# Lipo_Charger1.net
KiCad netlist of a schematic drawn in Altium Designer
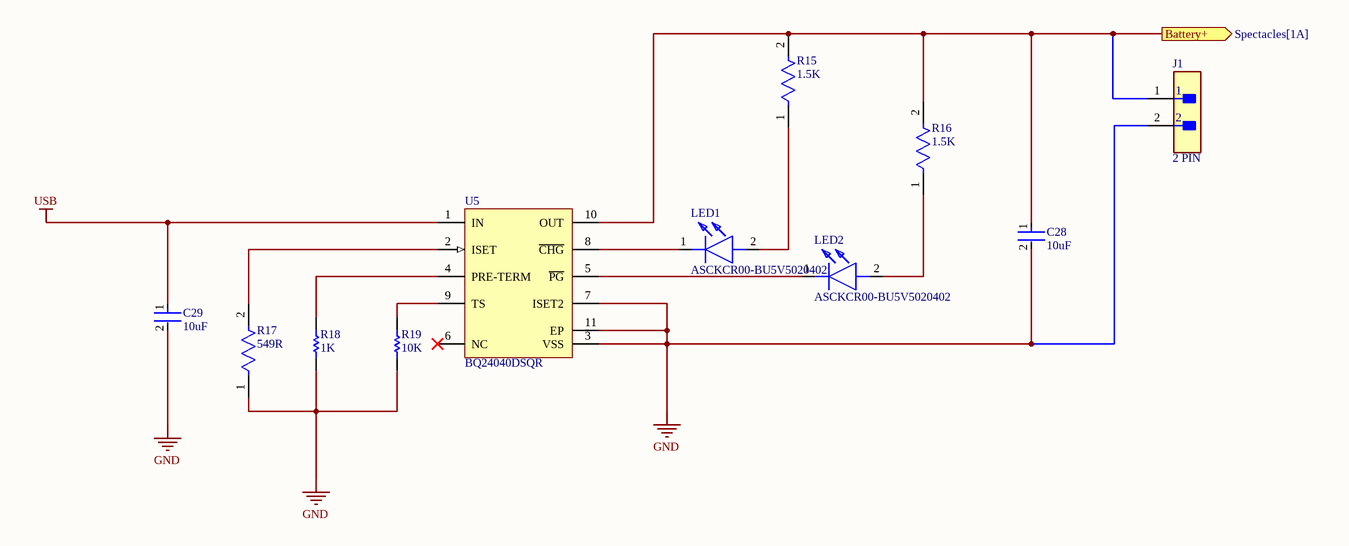
[diagram p0: Lipo Charger1.SchDoc]

(export (version "E")
  (design (tool "Eeschema 10.0.6"))
  (components
    (comp (ref "C28")
      (value "10uF")
      (footprint "FP-CL10-IPC_A")
      (description "Cap Ceramic 100nF 50V X7R ±10% Pad SMD 0603 +125°C T/R")
      (fields (field (name "VOLTAGE") "50V") (field (name "TOLERANCE") "10%"))
      (libsource (lib "Altium Content Vault") (part "b4654b650e69147ec39a6b967a45e02"))
    )
    (comp (ref "C29")
      (value "10uF")
      (footprint "FP-CL10-IPC_A")
      (description "Cap Ceramic 100nF 50V X7R ±10% Pad SMD 0603 +125°C T/R")
      (fields (field (name "VOLTAGE") "50V") (field (name "TOLERANCE") "10%"))
      (libsource (lib "Altium Content Vault") (part "b4654b650e69147ec39a6b967a45e02"))
    )
    (comp (ref "J1")
      (value "2 PIN")
      (footprint "FP-B2B-XH-AM_LF_SN-MFG")
      (description "CONN HEADER VERT 2POS 2.5MM")
      (libsource (lib "Altium Content Vault") (part "3bc925449376181038e59eaffc5286c"))
    )
    (comp (ref "LED1")
      (value "ASCKCR00-BU5V5020402")
      (footprint "SamacSys:ASCKCR00BU5V5020402")
      (description "LED")
      (fields (field (name "MOUSER PART NUMBER") "630-ASCKCR00BU5V5020"))
      (libsource (lib "*") (part "ASCKCR00-BU5V5020402"))
    )
    (comp (ref "LED2")
      (value "ASCKCR00-BU5V5020402")
      (footprint "SamacSys:ASCKCR00BU5V5020402")
      (description "LED")
      (fields (field (name "MOUSER PART NUMBER") "630-ASCKCR00BU5V5020"))
      (libsource (lib "*") (part "ASCKCR00-BU5V5020402"))
    )
    (comp (ref "R15")
      (value "1.5K")
      (footprint "FP-CRCW0603-e3-IPC_A")
      (description "RES Thick Film, 1.5kΩ, 1%, 0.1W, 100ppm/°C, 0603")
      (fields (field (name "TOLERANCE") "1%"))
      (libsource (lib "Altium Content Vault") (part "1029c3af85768c4190bb7ad29bc67b5"))
    )
    (comp (ref "R16")
      (value "1.5K")
      (footprint "FP-CRCW0603-e3-IPC_A")
      (description "RES Thick Film, 1.5kΩ, 1%, 0.1W, 100ppm/°C, 0603")
      (fields (field (name "TOLERANCE") "1%"))
      (libsource (lib "Altium Content Vault") (part "1029c3af85768c4190bb7ad29bc67b5"))
    )
    (comp (ref "R17")
      (value "549R")
      (footprint "FP-CRCW0603-e3-IPC_B")
      (description "RES Thick Film, 549Ω, 1%, 0.1W, 100ppm/°C, 0603")
      (fields (field (name "TOLERANCE") "1%"))
      (libsource (lib "Altium Content Vault") (part "1029c3af85768c4190bb7ad29bc67b5"))
    )
    (comp (ref "R18")
      (value "1K")
      (footprint "RESC1609X50X30NL8T20")
      (description "Chip Resistor, 10 KOhm, +/- 1%, 100 mW, -55 to 155 degC, 0603 (1608 Metric), RoHS, Tape and Reel")
      (fields (field (name "MANUFACTURER") "Vishay Semiconductor"))
      (libsource (lib "Altium Content Vault") (part "RES-2"))
    )
    (comp (ref "R19")
      (value "10K")
      (footprint "RESC1609X50X30NL8T20")
      (description "Chip Resistor, 10 KOhm, +/- 1%, 100 mW, -55 to 155 degC, 0603 (1608 Metric), RoHS, Tape and Reel")
      (fields (field (name "MANUFACTURER") "Vishay Semiconductor"))
      (libsource (lib "Altium Content Vault") (part "RES-2"))
    )
    (comp (ref "U5")
      (value "BQ24040DSQR")
      (footprint "DSQ0010A_V")
      (fields (field (name "MANUFACTURER") "Texas Instruments"))
      (libsource (lib "Altium Content Vault") (part "TI-BQ24040DSQ10-1500X900TP"))
    )
  )
  (nets
    (net (code "1") (name "/Battery+") (class "Default")
      (node (ref "C28") (pin "1") (pinfunction "1_1") (pintype "passive"))
      (node (ref "J1") (pin "1") (pinfunction "1_1") (pintype "passive"))
      (node (ref "R15") (pin "2") (pinfunction "2_2") (pintype "passive"))
      (node (ref "R16") (pin "2") (pinfunction "2_2") (pintype "passive"))
      (node (ref "U5") (pin "10") (pinfunction "OUT_10") (pintype "power_in"))
    )
    (net (code "2") (name "GND") (class "Default")
      (node (ref "C28") (pin "2") (pinfunction "2_2") (pintype "passive"))
      (node (ref "C29") (pin "2") (pinfunction "2_2") (pintype "passive"))
      (node (ref "J1") (pin "2") (pinfunction "2_2") (pintype "passive"))
      (node (ref "R17") (pin "1") (pinfunction "1_1") (pintype "passive"))
      (node (ref "R18") (pin "1") (pinfunction "1_1") (pintype "passive"))
      (node (ref "R19") (pin "1") (pinfunction "1_1") (pintype "passive"))
      (node (ref "U5") (pin "11") (pinfunction "EP_11") (pintype "power_in"))
      (node (ref "U5") (pin "3") (pinfunction "VSS_3") (pintype "power_in"))
      (node (ref "U5") (pin "7") (pinfunction "ISET2_7") (pintype "passive"))
    )
    (net (code "3") (name "Net-(LED1-A)") (class "Default")
      (node (ref "LED1") (pin "2") (pinfunction "A_2") (pintype "passive"))
      (node (ref "R15") (pin "1") (pinfunction "1_1") (pintype "passive"))
    )
    (net (code "4") (name "Net-(LED1-K)") (class "Default")
      (node (ref "LED1") (pin "1") (pinfunction "K_1") (pintype "passive"))
      (node (ref "U5") (pin "8") (pinfunction "~{CHG}_8") (pintype "tri_state"))
    )
    (net (code "5") (name "Net-(LED2-A)") (class "Default")
      (node (ref "LED2") (pin "2") (pinfunction "A_2") (pintype "passive"))
      (node (ref "R16") (pin "1") (pinfunction "1_1") (pintype "passive"))
    )
    (net (code "6") (name "Net-(LED2-K)") (class "Default")
      (node (ref "LED2") (pin "1") (pinfunction "K_1") (pintype "passive"))
      (node (ref "U5") (pin "5") (pinfunction "~{PG}_5") (pintype "tri_state"))
    )
    (net (code "7") (name "Net-(U5-ISET)") (class "Default")
      (node (ref "R17") (pin "2") (pinfunction "2_2") (pintype "passive"))
      (node (ref "U5") (pin "2") (pinfunction "ISET_2") (pintype "input"))
    )
    (net (code "8") (name "Net-(U5-PRE-TERM)") (class "Default")
      (node (ref "R18") (pin "2") (pinfunction "2_2") (pintype "passive"))
      (node (ref "U5") (pin "4") (pinfunction "PRE-TERM_4") (pintype "passive"))
    )
    (net (code "9") (name "Net-(U5-TS)") (class "Default")
      (node (ref "R19") (pin "2") (pinfunction "2_2") (pintype "passive"))
      (node (ref "U5") (pin "9") (pinfunction "TS_9") (pintype "passive"))
    )
    (net (code "10") (name "USB") (class "Default")
      (node (ref "C29") (pin "1") (pinfunction "1_1") (pintype "passive"))
      (node (ref "U5") (pin "1") (pinfunction "IN_1") (pintype "power_in"))
    )
    (net (code "11") (name "unconnected-(U5-NC-Pad6)") (class "Default")
      (node (ref "U5") (pin "6") (pinfunction "NC_6") (pintype "passive+no_connect"))
    )
  )
)
